# BMS028B_Interface.net
KiCad netlist of a schematic drawn in Altium Designer
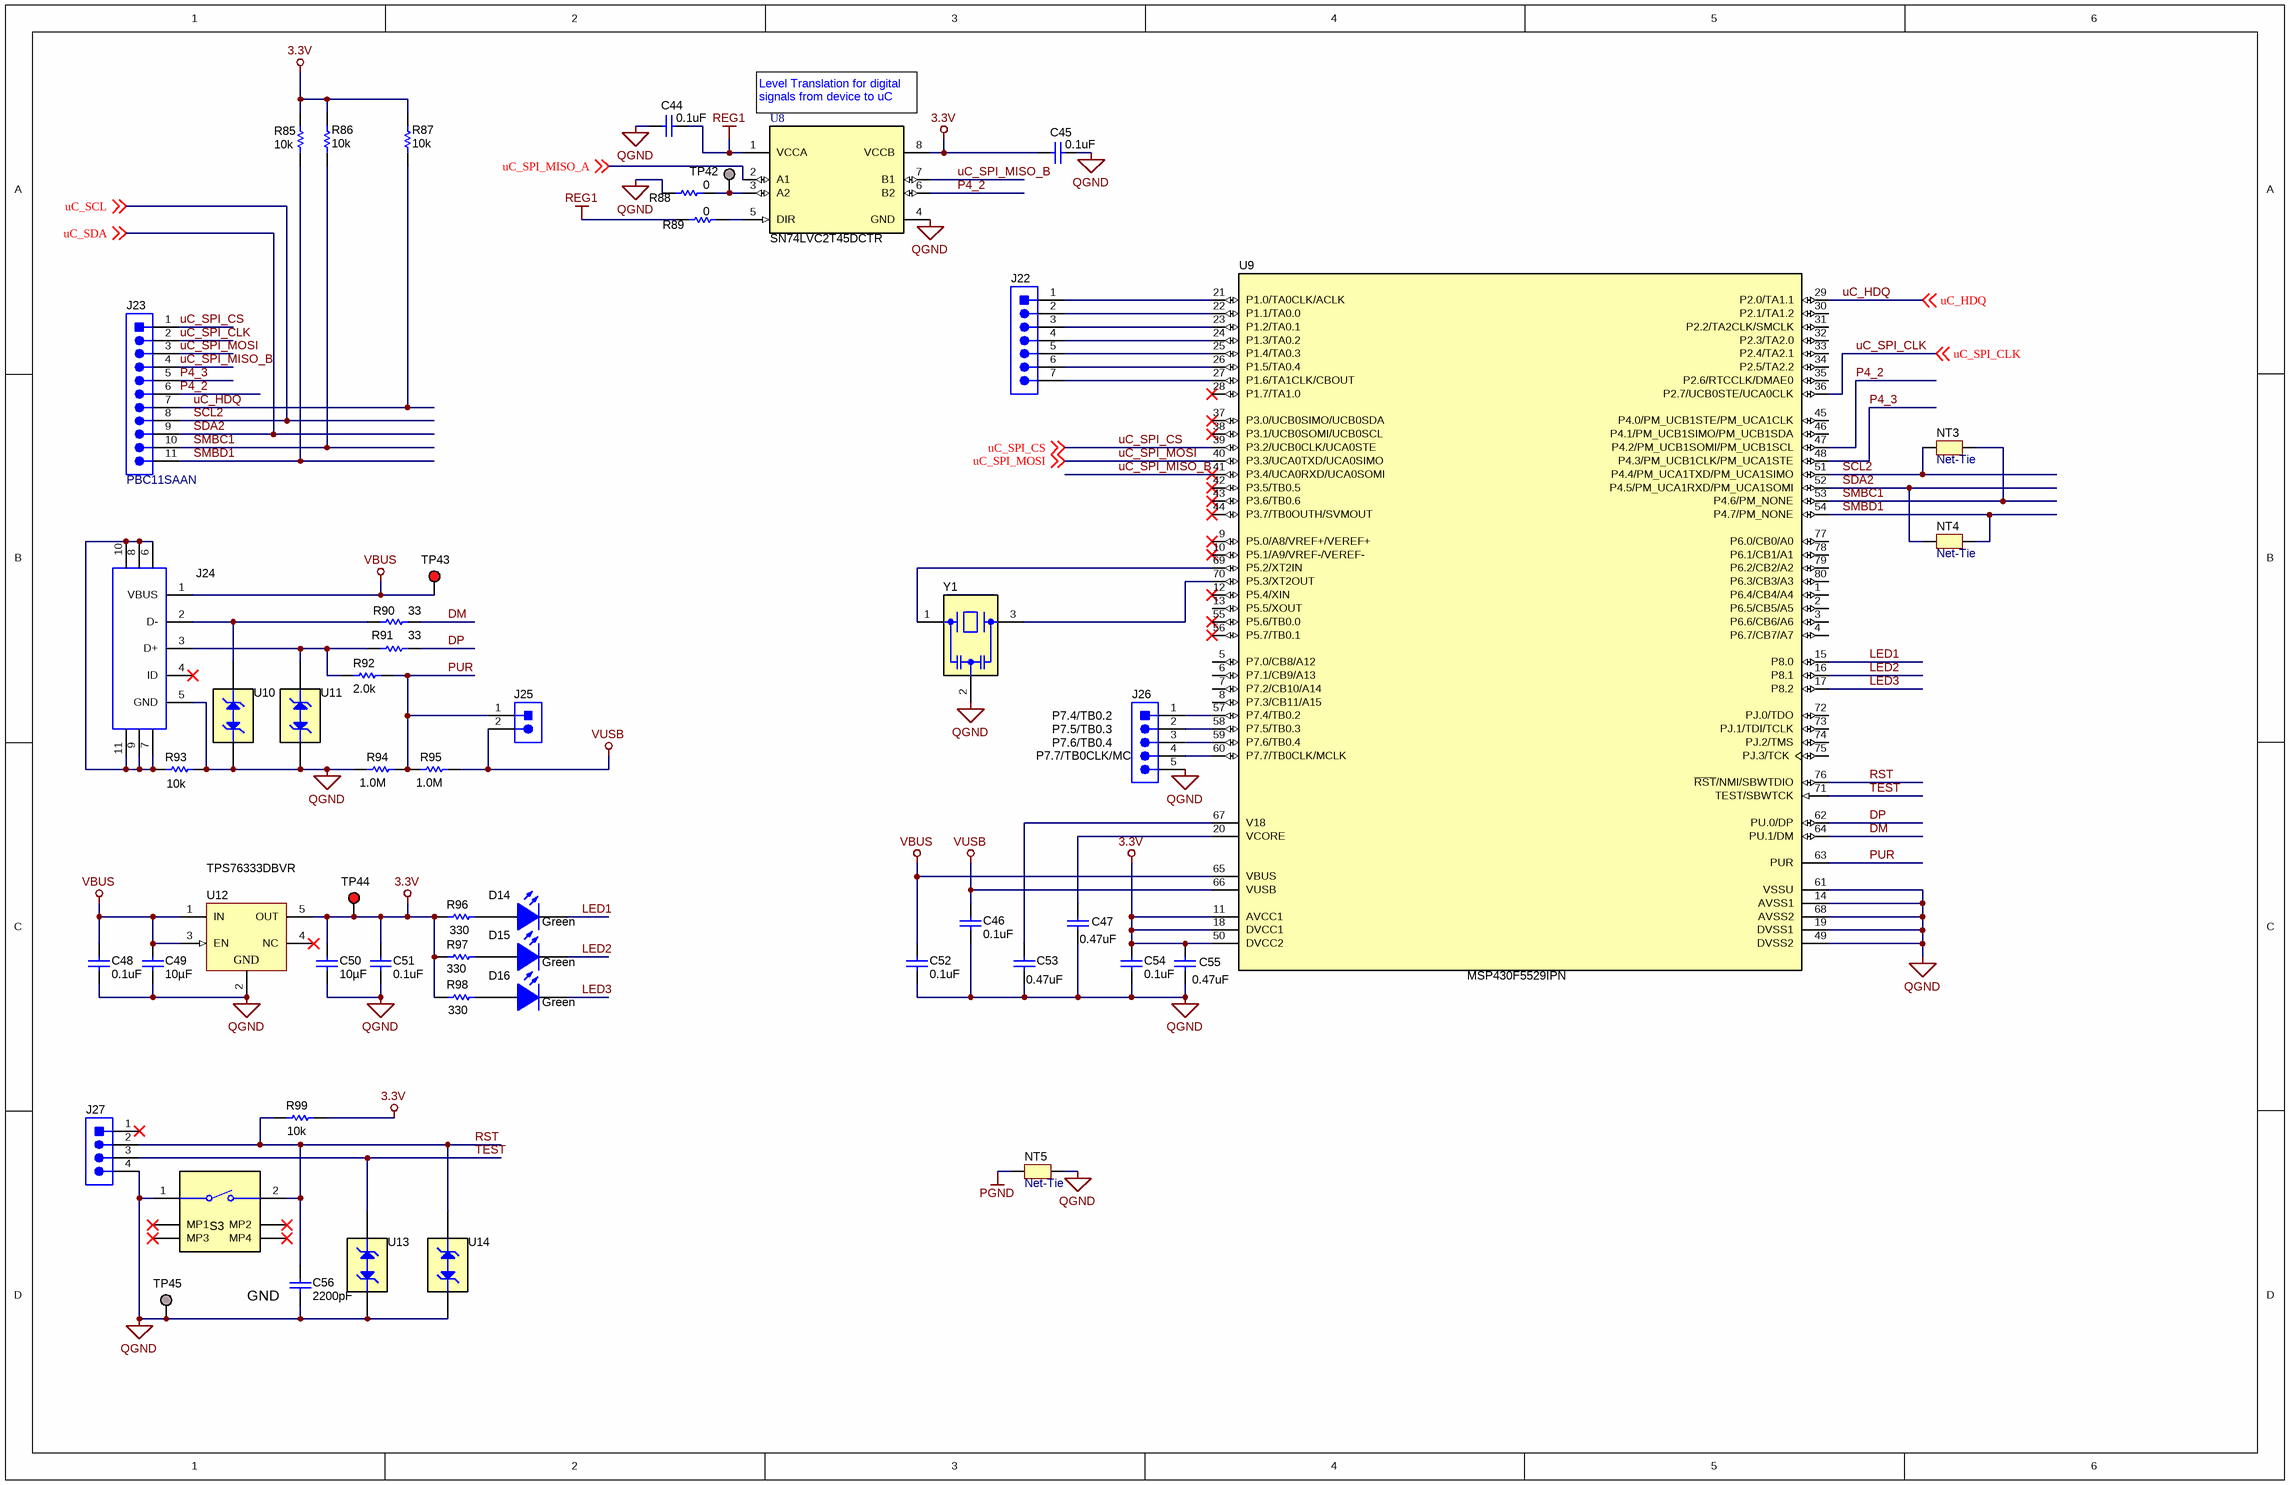
[diagram p0: BMS028B_Interface.SchDoc]

(export (version "E")
  (design (tool "Eeschema 10.0.6"))
  (components
    (comp (ref "C44")
      (value "885012205037")
      (footprint "0402")
      (description "CAP, CERM, 0.1 uF, 16 V, +/- 10%, X7R, 0402")
      (fields
        (field (name "VALUEDISPLAYED") "0.1uF")
        (field (name "MANUFACTURER") "Wurth Elektronik")
        (field (name "PUBLISHER") "Texas Instruments")
      )
      (libsource (lib "Altium Vault - TI") (part "Capacitor"))
    )
    (comp (ref "C45")
      (value "885012205037")
      (footprint "0402")
      (description "CAP, CERM, 0.1 uF, 16 V, +/- 10%, X7R, 0402")
      (fields
        (field (name "VALUEDISPLAYED") "0.1uF")
        (field (name "MANUFACTURER") "Wurth Elektronik")
        (field (name "PUBLISHER") "Texas Instruments")
      )
      (libsource (lib "Altium Vault - TI") (part "Capacitor"))
    )
    (comp (ref "C46")
      (value "885012205037")
      (footprint "0402")
      (description "CAP, CERM, 0.1 uF, 16 V, +/- 10%, X7R, 0402")
      (fields
        (field (name "VALUEDISPLAYED") "0.1uF")
        (field (name "MANUFACTURER") "Wurth Elektronik")
        (field (name "PUBLISHER") "Texas Instruments")
      )
      (libsource (lib "Altium Vault - TI") (part "Capacitor"))
    )
    (comp (ref "C47")
      (value "Capacitor")
      (footprint "0402")
      (description "CAP, CERM, 0.47 uF, 6.3 V, +/- 10%, X5R, 0402")
      (fields
        (field (name "PARTNUMBER") "04026D474KAT2A")
        (field (name "VALUEDISPLAYED") "0.47uF")
        (field (name "MANUFACTURER") "AVX")
        (field (name "PUBLISHER") "Texas Instruments")
      )
      (libsource (lib "Altium Vault - TI") (part "Capacitor"))
    )
    (comp (ref "C48")
      (value "885012205037")
      (footprint "0402")
      (description "CAP, CERM, 0.1 uF, 16 V, +/- 10%, X7R, 0402")
      (fields
        (field (name "VALUEDISPLAYED") "0.1uF")
        (field (name "MANUFACTURER") "Wurth Elektronik")
        (field (name "PUBLISHER") "Texas Instruments")
      )
      (libsource (lib "Altium Vault - TI") (part "Capacitor"))
    )
    (comp (ref "C49")
      (value "CL21A106KOQNNNG")
      (footprint "0805_HV")
      (description "CAP, CERM, 10 µF, 16 V,+/- 10%, X5R, 0805")
      (fields
        (field (name "VALUEDISPLAYED") "10µF")
        (field (name "MANUFACTURER") "Samsung Electro-Mechanics")
      )
      (libsource (lib "Altium Vault - TI") (part "Capacitor"))
    )
    (comp (ref "C50")
      (value "CL21A106KOQNNNG")
      (footprint "0805_HV")
      (description "CAP, CERM, 10 µF, 16 V,+/- 10%, X5R, 0805")
      (fields
        (field (name "VALUEDISPLAYED") "10µF")
        (field (name "MANUFACTURER") "Samsung Electro-Mechanics")
      )
      (libsource (lib "Altium Vault - TI") (part "Capacitor"))
    )
    (comp (ref "C51")
      (value "885012205037")
      (footprint "0402")
      (description "CAP, CERM, 0.1 uF, 16 V, +/- 10%, X7R, 0402")
      (fields
        (field (name "VALUEDISPLAYED") "0.1uF")
        (field (name "MANUFACTURER") "Wurth Elektronik")
        (field (name "PUBLISHER") "Texas Instruments")
      )
      (libsource (lib "Altium Vault - TI") (part "Capacitor"))
    )
    (comp (ref "C52")
      (value "885012205037")
      (footprint "0402")
      (description "CAP, CERM, 0.1 uF, 16 V, +/- 10%, X7R, 0402")
      (fields
        (field (name "VALUEDISPLAYED") "0.1uF")
        (field (name "MANUFACTURER") "Wurth Elektronik")
        (field (name "PUBLISHER") "Texas Instruments")
      )
      (libsource (lib "Altium Vault - TI") (part "Capacitor"))
    )
    (comp (ref "C53")
      (value "Capacitor")
      (footprint "0402")
      (description "CAP, CERM, 0.47 uF, 6.3 V, +/- 10%, X5R, 0402")
      (fields
        (field (name "PARTNUMBER") "04026D474KAT2A")
        (field (name "VALUEDISPLAYED") "0.47uF")
        (field (name "MANUFACTURER") "AVX")
        (field (name "PUBLISHER") "Texas Instruments")
      )
      (libsource (lib "Altium Vault - TI") (part "Capacitor"))
    )
    (comp (ref "C54")
      (value "885012205037")
      (footprint "0402")
      (description "CAP, CERM, 0.1 uF, 16 V, +/- 10%, X7R, 0402")
      (fields
        (field (name "VALUEDISPLAYED") "0.1uF")
        (field (name "MANUFACTURER") "Wurth Elektronik")
        (field (name "PUBLISHER") "Texas Instruments")
      )
      (libsource (lib "Altium Vault - TI") (part "Capacitor"))
    )
    (comp (ref "C55")
      (value "Capacitor")
      (footprint "0402")
      (description "CAP, CERM, 0.47 uF, 6.3 V, +/- 10%, X5R, 0402")
      (fields
        (field (name "PARTNUMBER") "04026D474KAT2A")
        (field (name "VALUEDISPLAYED") "0.47uF")
        (field (name "MANUFACTURER") "AVX")
        (field (name "PUBLISHER") "Texas Instruments")
      )
      (libsource (lib "Altium Vault - TI") (part "Capacitor"))
    )
    (comp (ref "C56")
      (value "885012205008")
      (footprint "0402")
      (description "CAP, CERM, 2200 pF, 10 V, +/- 10%, X7R, 0402")
      (fields
        (field (name "VALUEDISPLAYED") "2200pF")
        (field (name "MANUFACTURER") "Wurth Elektronik")
        (field (name "PUBLISHER") "Texas Instruments")
      )
      (libsource (lib "Altium Vault - TI") (part "Capacitor"))
    )
    (comp (ref "D14")
      (value "Green")
      (footprint "WL-SMCW_GREEN")
      (description "LED, Green, SMD")
      (fields (field (name "MANUFACTURER") "Wurth Elektronik") (field (name "PARTNUMBER") "150060VS75000"))
      (libsource (lib "Altium Vault - TI") (part "CMP-0002894-2"))
    )
    (comp (ref "D15")
      (value "Green")
      (footprint "WL-SMCW_GREEN")
      (description "LED, Green, SMD")
      (fields (field (name "MANUFACTURER") "Wurth Elektronik") (field (name "PARTNUMBER") "150060VS75000"))
      (libsource (lib "Altium Vault - TI") (part "CMP-0002894-2"))
    )
    (comp (ref "D16")
      (value "Green")
      (footprint "WL-SMCW_GREEN")
      (description "LED, Green, SMD")
      (fields (field (name "MANUFACTURER") "Wurth Elektronik") (field (name "PARTNUMBER") "150060VS75000"))
      (libsource (lib "Altium Vault - TI") (part "CMP-0002894-2"))
    )
    (comp (ref "J22")
      (value "PBC07SAAN")
      (footprint "Sullins_xxC07SAAN")
      (description "Header, 2.54 mm, 7x1, Gold, TH")
      (fields
        (field (name "MANUFACTURER") "Sullins Connector Solutions")
        (field (name "PUBLISHER") "Texas Instruments")
      )
      (libsource (lib "Altium Vault - TI") (part "CMP-0054584-1"))
    )
    (comp (ref "J23")
      (value "PBC11SAAN")
      (footprint "Sullins_xxC11SAAN")
      (description "Header, 2.54 mm, 11x1, Gold, TH")
      (fields
        (field (name "MANUFACTURER") "Sullins Connector Solutions")
        (field (name "PUBLISHER") "Texas Instruments")
      )
      (libsource (lib "Altium Vault - TI") (part "Header_11x1"))
    )
    (comp (ref "J24")
      (value "CONN_USB_5Pos-6Shld")
      (footprint "Molex_47346-1001")
      (description "Receptacle, Micro-USB Type B, 0.65 mm, 5x1, R/A, Bottom Mount SMT")
      (fields
        (field (name "PARTNUMBER") "47346-1001")
        (field (name "MANUFACTURER") "Molex")
        (field (name "SYMBOLCREATOR") "a0411947")
        (field (name "PUBLISHER") "Texas Instruments")
      )
      (libsource (lib "Altium Vault - TI") (part "CONN_USB_5Pos-6Shld"))
    )
    (comp (ref "J25")
      (value "61300211121")
      (footprint "WURTH_61300211121")
      (description "Header, 2.54 mm, 2x1, Gold, TH")
      (fields (field (name "MANUFACTURER") "Wurth Elektronik"))
      (libsource (lib "Altium Vault - TI") (part "CMP-0054794-2"))
    )
    (comp (ref "J26")
      (value "PEC05SAAN")
      (footprint "Sullins_PxC05SAAN")
      (description "Header, 2.54mm, 5x1, Tin, TH")
      (fields
        (field (name "MANUFACTURER") "Sullins Connector Solutions")
        (field (name "PUBLISHER") "Texas Instruments")
      )
      (libsource (lib "Altium Vault - TI") (part "CMP-0054597-1"))
    )
    (comp (ref "J27")
      (value "22284043")
      (footprint "Molex_0022284043")
      (description "Header, 2.54mm, 4x1, Tin, TH")
      (fields (field (name "MANUFACTURER") "Molex") (field (name "PUBLISHER") "Texas Instruments"))
      (libsource (lib "Altium Vault - TI") (part "CMP-0055331-1"))
    )
    (comp (ref "NT3")
      (value "Net-Tie")
      (footprint "Net-Tie_10mil")
      (description "Single point connection between nets.")
      (libsource (lib "") (part "Net-Tie_1"))
    )
    (comp (ref "NT4")
      (value "Net-Tie")
      (footprint "Net-Tie_10mil")
      (description "Single point connection between nets.")
      (libsource (lib "") (part "Net-Tie_1"))
    )
    (comp (ref "NT5")
      (value "Net-Tie")
      (footprint "Net-Tie_0805_HV_NoOverlay")
      (description "Single point connection between nets.")
      (libsource (lib "Altium Vault - TI") (part "Net-Tie"))
    )
    (comp (ref "R85")
      (value "CRCW060310K0JNEA")
      (footprint "0603")
      (description "RES, 10 k, 5%, 0.1 W, AEC-Q200 Grade 0, 0603")
      (fields (field (name "MANUFACTURER") "Vishay-Dale") (field (name "VALUEDISPLAYED") "10k"))
      (libsource (lib "Altium Vault - TI") (part "Resistor"))
    )
    (comp (ref "R86")
      (value "CRCW060310K0JNEA")
      (footprint "0603")
      (description "RES, 10 k, 5%, 0.1 W, AEC-Q200 Grade 0, 0603")
      (fields (field (name "MANUFACTURER") "Vishay-Dale") (field (name "VALUEDISPLAYED") "10k"))
      (libsource (lib "Altium Vault - TI") (part "CMP-0025701-4"))
    )
    (comp (ref "R87")
      (value "CRCW060310K0JNEA")
      (footprint "0603")
      (description "RES, 10 k, 5%, 0.1 W, AEC-Q200 Grade 0, 0603")
      (fields (field (name "MANUFACTURER") "Vishay-Dale") (field (name "VALUEDISPLAYED") "10k"))
      (libsource (lib "Altium Vault - TI") (part "Resistor"))
    )
    (comp (ref "R88")
      (value "CRCW06030000Z0EA")
      (footprint "0603")
      (description "RES, 0, 5%, 0.1 W, AEC-Q200 Grade 0, 0603")
      (fields (field (name "MANUFACTURER") "Vishay-Dale") (field (name "VALUEDISPLAYED") "0"))
      (libsource (lib "Altium Vault - TI") (part "Resistor"))
    )
    (comp (ref "R89")
      (value "CRCW06030000Z0EA")
      (footprint "0603")
      (description "RES, 0, 5%, 0.1 W, AEC-Q200 Grade 0, 0603")
      (fields (field (name "MANUFACTURER") "Vishay-Dale") (field (name "VALUEDISPLAYED") "0"))
      (libsource (lib "Altium Vault - TI") (part "Resistor"))
    )
    (comp (ref "R90")
      (value "Resistor")
      (footprint "0402")
      (description "RES, 33, 5%, 0.063 W, AEC-Q200 Grade 0, 0402")
      (fields
        (field (name "PARTNUMBER") "CRCW040233R0JNED")
        (field (name "VALUEDISPLAYED") "33")
        (field (name "MANUFACTURER") "Vishay-Dale")
        (field (name "PUBLISHER") "Texas Instruments")
      )
      (libsource (lib "Altium Vault - TI") (part "Resistor"))
    )
    (comp (ref "R91")
      (value "Resistor")
      (footprint "0402")
      (description "RES, 33, 5%, 0.063 W, AEC-Q200 Grade 0, 0402")
      (fields
        (field (name "PARTNUMBER") "CRCW040233R0JNED")
        (field (name "VALUEDISPLAYED") "33")
        (field (name "MANUFACTURER") "Vishay-Dale")
        (field (name "PUBLISHER") "Texas Instruments")
      )
      (libsource (lib "Altium Vault - TI") (part "Resistor"))
    )
    (comp (ref "R92")
      (value "Resistor")
      (footprint "0402")
      (description "RES, 2.0 k, 5%, 0.063 W, AEC-Q200 Grade 0, 0402")
      (fields
        (field (name "PARTNUMBER") "CRCW04022K00JNED")
        (field (name "VALUEDISPLAYED") "2.0k")
        (field (name "MANUFACTURER") "Vishay-Dale")
        (field (name "PUBLISHER") "Texas Instruments")
      )
      (libsource (lib "Altium Vault - TI") (part "Resistor"))
    )
    (comp (ref "R93")
      (value "Resistor")
      (footprint "0402")
      (description "RES, 10 k, 5%, 0.063 W, AEC-Q200 Grade 0, 0402")
      (fields
        (field (name "PARTNUMBER") "CRCW040210K0JNED")
        (field (name "VALUEDISPLAYED") "10k")
        (field (name "MANUFACTURER") "Vishay-Dale")
        (field (name "PUBLISHER") "Texas Instruments")
      )
      (libsource (lib "Altium Vault - TI") (part "Resistor"))
    )
    (comp (ref "R94")
      (value "Resistor")
      (footprint "0402")
      (description "RES, 1.0 M, 5%, 0.063 W, AEC-Q200 Grade 0, 0402")
      (fields
        (field (name "PARTNUMBER") "CRCW04021M00JNED")
        (field (name "VALUEDISPLAYED") "1.0M")
        (field (name "MANUFACTURER") "Vishay-Dale")
        (field (name "PUBLISHER") "Texas Instruments")
      )
      (libsource (lib "Altium Vault - TI") (part "Resistor"))
    )
    (comp (ref "R95")
      (value "Resistor")
      (footprint "0402")
      (description "RES, 1.0 M, 5%, 0.063 W, AEC-Q200 Grade 0, 0402")
      (fields
        (field (name "PARTNUMBER") "CRCW04021M00JNED")
        (field (name "VALUEDISPLAYED") "1.0M")
        (field (name "MANUFACTURER") "Vishay-Dale")
        (field (name "PUBLISHER") "Texas Instruments")
      )
      (libsource (lib "Altium Vault - TI") (part "Resistor"))
    )
    (comp (ref "R96")
      (value "Resistor")
      (footprint "0402")
      (description "RES, 330, 1%, 0.1 W, AEC-Q200 Grade 0, 0402")
      (fields
        (field (name "PARTNUMBER") "ERJ-2RKF3300X")
        (field (name "VALUEDISPLAYED") "330")
        (field (name "MANUFACTURER") "Panasonic")
        (field (name "PUBLISHER") "Texas Instruments")
      )
      (libsource (lib "Altium Vault - TI") (part "Resistor"))
    )
    (comp (ref "R97")
      (value "Resistor")
      (footprint "0402")
      (description "RES, 330, 1%, 0.1 W, AEC-Q200 Grade 0, 0402")
      (fields
        (field (name "PARTNUMBER") "ERJ-2RKF3300X")
        (field (name "VALUEDISPLAYED") "330")
        (field (name "MANUFACTURER") "Panasonic")
        (field (name "PUBLISHER") "Texas Instruments")
      )
      (libsource (lib "Altium Vault - TI") (part "Resistor"))
    )
    (comp (ref "R98")
      (value "Resistor")
      (footprint "0402")
      (description "RES, 330, 1%, 0.1 W, AEC-Q200 Grade 0, 0402")
      (fields
        (field (name "PARTNUMBER") "ERJ-2RKF3300X")
        (field (name "VALUEDISPLAYED") "330")
        (field (name "MANUFACTURER") "Panasonic")
        (field (name "PUBLISHER") "Texas Instruments")
      )
      (libsource (lib "Altium Vault - TI") (part "Resistor"))
    )
    (comp (ref "R99")
      (value "Resistor")
      (footprint "0402")
      (description "RES, 10 k, 5%, 0.063 W, AEC-Q200 Grade 0, 0402")
      (fields
        (field (name "PARTNUMBER") "CRCW040210K0JNED")
        (field (name "VALUEDISPLAYED") "10k")
        (field (name "MANUFACTURER") "Vishay-Dale")
        (field (name "PUBLISHER") "Texas Instruments")
      )
      (libsource (lib "Altium Vault - TI") (part "Resistor"))
    )
    (comp (ref "S3")
      (value "PTS820 J20M SMTR LFS")
      (footprint "SW_PTS820")
      (description "Switch, SPST-NO,  Off-Mom, 0.05A, 12VDC, SMD")
      (fields (field (name "MANUFACTURER") "C&K Components") (field (name "PUBLISHER") "Texas Instruments"))
      (libsource (lib "Altium Vault - TI") (part "SW_SPST_12_4MP"))
    )
    (comp (ref "TP42")
      (value "TESTPOINT")
      (footprint "TP_50MIL-25MILHOLE")
      (description "TEST POINT.  No entry in BOM.")
      (libsource (lib "Altium Vault - TI") (part "TESTPOINT"))
    )
    (comp (ref "TP43")
      (value "5005")
      (footprint "Keystone5005")
      (description "Test Point, Compact, Red, TH")
      (fields (field (name "MANUFACTURER") "Keystone") (field (name "PUBLISHER") "Texas Instruments"))
      (libsource (lib "Altium Vault - TI") (part "5005"))
    )
    (comp (ref "TP44")
      (value "5005")
      (footprint "Keystone5005")
      (description "Test Point, Compact, Red, TH")
      (fields (field (name "MANUFACTURER") "Keystone") (field (name "PUBLISHER") "Texas Instruments"))
      (libsource (lib "Altium Vault - TI") (part "5005"))
    )
    (comp (ref "TP45")
      (value "TESTPOINT")
      (footprint "TP_SM_1MM")
      (description "1mm Test Point, SMT")
      (fields
        (field (name "PARTNUMBER") "TP_SM_1MM")
        (field (name "MANUFACTURER") "Any")
        (field (name "PUBLISHER") "Texas Instruments")
      )
      (libsource (lib "Altium Vault - TI") (part "TESTPOINT"))
    )
    (comp (ref "U8")
      (value "SN74LVC2T45DCTR")
      (footprint "DCT0008A_N")
      (fields
        (field (name "MANUFACTURER") "Texas Instruments")
        (field (name "GENERIC PART NUMBER") "SN74LVC2T45")
        (field (name "PARTNUMBER") "SN74LVC2T45DCTR")
      )
      (libsource (lib "Altium Vault - TI") (part "TI-SN74XVC2T45-8"))
    )
    (comp (ref "U9")
      (value "CMP-0038965-1")
      (footprint "PN0080A_N")
      (fields (field (name "PARTNUMBER") "MSP430F5529IPN") (field (name "MANUFACTURER") "Texas Instruments"))
      (libsource (lib "Altium Vault - TI") (part "TI-MSP430F552X_A-PN80"))
    )
    (comp (ref "U10")
      (value "TPD1E10B06DPYT")
      (footprint "DPY0002A")
      (description "Single-Channel ESD in 0402 Package With 10pF Capacitance and 6V Breakdown, DPY0002A (X1SON-2)")
      (fields
        (field (name "MANUFACTURER") "Texas Instruments")
        (field (name "ALTERNATE PARTNUMBER") "TPD1E10B06DPYR")
      )
      (libsource (lib "Altium Vault - TI") (part "CMP-0043094-3"))
    )
    (comp (ref "U11")
      (value "TPD1E10B06DPYT")
      (footprint "DPY0002A")
      (description "Single-Channel ESD in 0402 Package With 10pF Capacitance and 6V Breakdown, DPY0002A (X1SON-2)")
      (fields
        (field (name "MANUFACTURER") "Texas Instruments")
        (field (name "ALTERNATE PARTNUMBER") "TPD1E10B06DPYR")
      )
      (libsource (lib "Altium Vault - TI") (part "CMP-0043094-3"))
    )
    (comp (ref "U12")
      (value "CMP-0035539-1")
      (footprint "DBV0005A_N")
      (fields (field (name "MANUFACTURER") "Texas Instruments") (field (name "PARTNUMBER") "TPS76333DBVR"))
      (libsource (lib "Altium Vault - TI") (part "CMP-0035539-1"))
    )
    (comp (ref "U13")
      (value "TPD1E10B06DPYT")
      (footprint "DPY0002A")
      (description "Single-Channel ESD in 0402 Package With 10pF Capacitance and 6V Breakdown, DPY0002A (X1SON-2)")
      (fields
        (field (name "MANUFACTURER") "Texas Instruments")
        (field (name "ALTERNATE PARTNUMBER") "TPD1E10B06DPYR")
      )
      (libsource (lib "Altium Vault - TI") (part "CMP-0043094-3"))
    )
    (comp (ref "U14")
      (value "TPD1E10B06DPYT")
      (footprint "DPY0002A")
      (description "Single-Channel ESD in 0402 Package With 10pF Capacitance and 6V Breakdown, DPY0002A (X1SON-2)")
      (fields
        (field (name "MANUFACTURER") "Texas Instruments")
        (field (name "ALTERNATE PARTNUMBER") "TPD1E10B06DPYR")
      )
      (libsource (lib "Altium Vault - TI") (part "CMP-0043094-3"))
    )
    (comp (ref "Y1")
      (value "CSTCR4M00G55B-R0")
      (footprint "Murata_CSTCR_G")
      (description "Resonator, 4 MHz, 39 pF, AEC-Q200 Grade 1, SMD")
      (fields (field (name "MANUFACTURER") "MuRata"))
      (libsource (lib "Altium Vault - TI") (part "CMP-0084387-1"))
    )
  )
  (nets
    (net (code "2") (name "/DM") (class "Default")
      (node (ref "R90") (pin "2") (pinfunction "2_2") (pintype "passive"))
      (node (ref "U9") (pin "64") (pinfunction "PU.1/DM_64") (pintype "bidirectional"))
    )
    (net (code "3") (name "/DP") (class "Default")
      (node (ref "R91") (pin "2") (pinfunction "2_2") (pintype "passive"))
      (node (ref "U9") (pin "62") (pinfunction "PU.0/DP_62") (pintype "bidirectional"))
    )
    (net (code "4") (name "/LED1") (class "Default")
      (node (ref "D14") (pin "1") (pinfunction "K_1") (pintype "passive"))
      (node (ref "U9") (pin "15") (pinfunction "P8.0_15") (pintype "bidirectional"))
    )
    (net (code "5") (name "/LED2") (class "Default")
      (node (ref "D15") (pin "1") (pinfunction "K_1") (pintype "passive"))
      (node (ref "U9") (pin "16") (pinfunction "P8.1_16") (pintype "bidirectional"))
    )
    (net (code "6") (name "/LED3") (class "Default")
      (node (ref "D16") (pin "1") (pinfunction "K_1") (pintype "passive"))
      (node (ref "U9") (pin "17") (pinfunction "P8.2_17") (pintype "bidirectional"))
    )
    (net (code "7") (name "/P4_2") (class "Default")
      (node (ref "J23") (pin "6") (pinfunction "6_6") (pintype "passive"))
      (node (ref "U8") (pin "6") (pinfunction "B2_6") (pintype "bidirectional"))
      (node (ref "U9") (pin "47") (pinfunction "P4.2/PM_UCB1SOMI/PM_UCB1SCL_47") (pintype "bidirectional"))
    )
    (net (code "8") (name "/P4_3") (class "Default")
      (node (ref "J23") (pin "5") (pinfunction "5_5") (pintype "passive"))
      (node (ref "U9") (pin "48") (pinfunction "P4.3/PM_UCB1CLK/PM_UCA1STE_48") (pintype "bidirectional"))
    )
    (net (code "9") (name "/PUR") (class "Default")
      (node (ref "J25") (pin "1") (pinfunction "1_1") (pintype "passive"))
      (node (ref "R92") (pin "1") (pinfunction "1_1") (pintype "passive"))
      (node (ref "R94") (pin "2") (pinfunction "2_2") (pintype "passive"))
      (node (ref "R95") (pin "1") (pinfunction "1_1") (pintype "passive"))
      (node (ref "U9") (pin "63") (pinfunction "PUR_63") (pintype "passive"))
    )
    (net (code "10") (name "/RST") (class "Default")
      (node (ref "C56") (pin "1") (pinfunction "1_1") (pintype "passive"))
      (node (ref "J27") (pin "2") (pinfunction "2_2") (pintype "passive"))
      (node (ref "R99") (pin "1") (pinfunction "1_1") (pintype "passive"))
      (node (ref "S3") (pin "2") (pinfunction "2_2") (pintype "passive"))
      (node (ref "U14") (pin "1") (pinfunction "K_1") (pintype "passive"))
      (node (ref "U9") (pin "76") (pinfunction "~{RST}/NMI/SBWTDIO_76") (pintype "bidirectional"))
    )
    (net (code "11") (name "/SMBC1") (class "Default")
      (node (ref "J23") (pin "10") (pinfunction "10_10") (pintype "passive"))
      (node (ref "NT3") (pin "2") (pinfunction "2_2") (pintype "passive"))
      (node (ref "R86") (pin "2") (pinfunction "2_2") (pintype "passive"))
      (node (ref "U9") (pin "53") (pinfunction "P4.6/PM_NONE_53") (pintype "bidirectional"))
    )
    (net (code "12") (name "/SMBD1") (class "Default")
      (node (ref "J23") (pin "11") (pinfunction "11_11") (pintype "passive"))
      (node (ref "NT4") (pin "2") (pinfunction "2_2") (pintype "passive"))
      (node (ref "R85") (pin "2") (pinfunction "2_2") (pintype "passive"))
      (node (ref "U9") (pin "54") (pinfunction "P4.7/PM_NONE_54") (pintype "bidirectional"))
    )
    (net (code "13") (name "/TEST") (class "Default")
      (node (ref "J27") (pin "3") (pinfunction "3_3") (pintype "passive"))
      (node (ref "U13") (pin "1") (pinfunction "K_1") (pintype "passive"))
      (node (ref "U9") (pin "71") (pinfunction "TEST/SBWTCK_71") (pintype "input"))
    )
    (net (code "14") (name "/uC_SPI_MISO_B") (class "Default")
      (node (ref "J23") (pin "4") (pinfunction "4_4") (pintype "passive"))
      (node (ref "U8") (pin "7") (pinfunction "B1_7") (pintype "bidirectional"))
      (node (ref "U9") (pin "41") (pinfunction "P3.4/UCA0RXD/UCA0SOMI_41") (pintype "bidirectional"))
    )
    (net (code "15") (name "3.3V") (class "Default")
      (node (ref "C45") (pin "2") (pinfunction "2_2") (pintype "passive"))
      (node (ref "C50") (pin "1") (pinfunction "1_1") (pintype "passive"))
      (node (ref "C51") (pin "1") (pinfunction "1_1") (pintype "passive"))
      (node (ref "C54") (pin "1") (pinfunction "1_1") (pintype "passive"))
      (node (ref "C55") (pin "1") (pinfunction "1_1") (pintype "passive"))
      (node (ref "R85") (pin "1") (pinfunction "1_1") (pintype "passive"))
      (node (ref "R86") (pin "1") (pinfunction "1_1") (pintype "passive"))
      (node (ref "R87") (pin "1") (pinfunction "1_1") (pintype "passive"))
      (node (ref "R96") (pin "2") (pinfunction "2_2") (pintype "passive"))
      (node (ref "R97") (pin "2") (pinfunction "2_2") (pintype "passive"))
      (node (ref "R98") (pin "2") (pinfunction "2_2") (pintype "passive"))
      (node (ref "R99") (pin "2") (pinfunction "2_2") (pintype "passive"))
      (node (ref "TP44") (pin "1") (pintype "passive"))
      (node (ref "U12") (pin "5") (pinfunction "OUT_5") (pintype "power_in"))
      (node (ref "U8") (pin "8") (pinfunction "VCCB_8") (pintype "power_in"))
      (node (ref "U9") (pin "11") (pinfunction "AVCC1_11") (pintype "power_in"))
      (node (ref "U9") (pin "18") (pinfunction "DVCC1_18") (pintype "power_in"))
      (node (ref "U9") (pin "50") (pinfunction "DVCC2_50") (pintype "power_in"))
    )
    (net (code "16") (name "Net-(D14-A)") (class "Default")
      (node (ref "D14") (pin "2") (pinfunction "A_2") (pintype "passive"))
      (node (ref "R96") (pin "1") (pinfunction "1_1") (pintype "passive"))
    )
    (net (code "17") (name "Net-(D15-A)") (class "Default")
      (node (ref "D15") (pin "2") (pinfunction "A_2") (pintype "passive"))
      (node (ref "R97") (pin "1") (pinfunction "1_1") (pintype "passive"))
    )
    (net (code "18") (name "Net-(D16-A)") (class "Default")
      (node (ref "D16") (pin "2") (pinfunction "A_2") (pintype "passive"))
      (node (ref "R98") (pin "1") (pinfunction "1_1") (pintype "passive"))
    )
    (net (code "19") (name "Net-(J24-D+)") (class "Default")
      (node (ref "J24") (pin "3") (pinfunction "D+_3") (pintype "passive"))
      (node (ref "R91") (pin "1") (pinfunction "1_1") (pintype "passive"))
      (node (ref "R92") (pin "2") (pinfunction "2_2") (pintype "passive"))
      (node (ref "U11") (pin "1") (pinfunction "K_1") (pintype "passive"))
    )
    (net (code "20") (name "Net-(J24-D-)") (class "Default")
      (node (ref "J24") (pin "2") (pinfunction "D-_2") (pintype "passive"))
      (node (ref "R90") (pin "1") (pinfunction "1_1") (pintype "passive"))
      (node (ref "U10") (pin "1") (pinfunction "K_1") (pintype "passive"))
    )
    (net (code "21") (name "Net-(J24-Pad10)") (class "Default")
      (node (ref "J24") (pin "10") (pinfunction "10_10") (pintype "passive"))
      (node (ref "J24") (pin "11") (pinfunction "11_11") (pintype "passive"))
      (node (ref "J24") (pin "6") (pinfunction "6_6") (pintype "passive"))
      (node (ref "J24") (pin "7") (pinfunction "7_7") (pintype "passive"))
      (node (ref "J24") (pin "8") (pinfunction "8_8") (pintype "passive"))
      (node (ref "J24") (pin "9") (pinfunction "9_9") (pintype "passive"))
      (node (ref "R93") (pin "2") (pinfunction "2_2") (pintype "passive"))
    )
    (net (code "22") (name "Net-(U8-A2)") (class "Default")
      (node (ref "R88") (pin "2") (pinfunction "2_2") (pintype "passive"))
      (node (ref "TP42") (pin "1") (pintype "passive"))
      (node (ref "U8") (pin "3") (pinfunction "A2_3") (pintype "bidirectional"))
    )
    (net (code "23") (name "Net-(U8-DIR)") (class "Default")
      (node (ref "R89") (pin "2") (pinfunction "2_2") (pintype "passive"))
      (node (ref "U8") (pin "5") (pinfunction "DIR_5") (pintype "input"))
    )
    (net (code "24") (name "Net-(U9-P1.0{slash}TA0CLK{slash}ACLK)") (class "Default")
      (node (ref "J22") (pin "1") (pinfunction "1_1") (pintype "passive"))
      (node (ref "U9") (pin "21") (pinfunction "P1.0/TA0CLK/ACLK_21") (pintype "bidirectional"))
    )
    (net (code "25") (name "Net-(U9-P1.1{slash}TA0.0)") (class "Default")
      (node (ref "J22") (pin "2") (pinfunction "2_2") (pintype "passive"))
      (node (ref "U9") (pin "22") (pinfunction "P1.1/TA0.0_22") (pintype "bidirectional"))
    )
    (net (code "26") (name "Net-(U9-P1.2{slash}TA0.1)") (class "Default")
      (node (ref "J22") (pin "3") (pinfunction "3_3") (pintype "passive"))
      (node (ref "U9") (pin "23") (pinfunction "P1.2/TA0.1_23") (pintype "bidirectional"))
    )
    (net (code "27") (name "Net-(U9-P1.3{slash}TA0.2)") (class "Default")
      (node (ref "J22") (pin "4") (pinfunction "4_4") (pintype "passive"))
      (node (ref "U9") (pin "24") (pinfunction "P1.3/TA0.2_24") (pintype "bidirectional"))
    )
    (net (code "28") (name "Net-(U9-P1.4{slash}TA0.3)") (class "Default")
      (node (ref "J22") (pin "5") (pinfunction "5_5") (pintype "passive"))
      (node (ref "U9") (pin "25") (pinfunction "P1.4/TA0.3_25") (pintype "bidirectional"))
    )
    (net (code "29") (name "Net-(U9-P1.5{slash}TA0.4)") (class "Default")
      (node (ref "J22") (pin "6") (pinfunction "6_6") (pintype "passive"))
      (node (ref "U9") (pin "26") (pinfunction "P1.5/TA0.4_26") (pintype "bidirectional"))
    )
    (net (code "30") (name "Net-(U9-P1.6{slash}TA1CLK{slash}CBOUT)") (class "Default")
      (node (ref "J22") (pin "7") (pinfunction "7_7") (pintype "passive"))
      (node (ref "U9") (pin "27") (pinfunction "P1.6/TA1CLK/CBOUT_27") (pintype "bidirectional"))
    )
    (net (code "31") (name "Net-(U9-P5.2{slash}XT2IN)") (class "Default")
      (node (ref "U9") (pin "69") (pinfunction "P5.2/XT2IN_69") (pintype "bidirectional"))
      (node (ref "Y1") (pin "1") (pinfunction "In_1") (pintype "passive"))
    )
    (net (code "32") (name "Net-(U9-P5.3{slash}XT2OUT)") (class "Default")
      (node (ref "U9") (pin "70") (pinfunction "P5.3/XT2OUT_70") (pintype "bidirectional"))
      (node (ref "Y1") (pin "3") (pinfunction "Out_3") (pintype "passive"))
    )
    (net (code "33") (name "Net-(U9-P7.4{slash}TB0.2)") (class "Default")
      (node (ref "J26") (pin "1") (pinfunction "1_1") (pintype "passive"))
      (node (ref "U9") (pin "57") (pinfunction "P7.4/TB0.2_57") (pintype "bidirectional"))
    )
    (net (code "34") (name "Net-(U9-P7.5{slash}TB0.3)") (class "Default")
      (node (ref "J26") (pin "2") (pinfunction "2_2") (pintype "passive"))
      (node (ref "U9") (pin "58") (pinfunction "P7.5/TB0.3_58") (pintype "bidirectional"))
    )
    (net (code "35") (name "Net-(U9-P7.6{slash}TB0.4)") (class "Default")
      (node (ref "J26") (pin "3") (pinfunction "3_3") (pintype "passive"))
      (node (ref "U9") (pin "59") (pinfunction "P7.6/TB0.4_59") (pintype "bidirectional"))
    )
    (net (code "36") (name "Net-(U9-P7.7{slash}TB0CLK{slash}MCLK)") (class "Default")
      (node (ref "J26") (pin "4") (pinfunction "4_4") (pintype "passive"))
      (node (ref "U9") (pin "60") (pinfunction "P7.7/TB0CLK/MCLK_60") (pintype "bidirectional"))
    )
    (net (code "37") (name "Net-(U9-V18)") (class "Default")
      (node (ref "C53") (pin "1") (pinfunction "1_1") (pintype "passive"))
      (node (ref "U9") (pin "67") (pinfunction "V18_67") (pintype "passive"))
    )
    (net (code "38") (name "Net-(U9-VCORE)") (class "Default")
      (node (ref "C47") (pin "1") (pinfunction "1_1") (pintype "passive"))
      (node (ref "U9") (pin "20") (pinfunction "VCORE_20") (pintype "passive"))
    )
    (net (code "39") (name "PGND") (class "Default")
      (node (ref "NT5") (pin "2") (pinfunction "2_2") (pintype "passive"))
    )
    (net (code "40") (name "QGND") (class "Default")
      (node (ref "C44") (pin "1") (pinfunction "1_1") (pintype "passive"))
      (node (ref "C45") (pin "1") (pinfunction "1_1") (pintype "passive"))
      (node (ref "C46") (pin "2") (pinfunction "2_2") (pintype "passive"))
      (node (ref "C47") (pin "2") (pinfunction "2_2") (pintype "passive"))
      (node (ref "C48") (pin "2") (pinfunction "2_2") (pintype "passive"))
      (node (ref "C49") (pin "2") (pinfunction "2_2") (pintype "passive"))
      (node (ref "C50") (pin "2") (pinfunction "2_2") (pintype "passive"))
      (node (ref "C51") (pin "2") (pinfunction "2_2") (pintype "passive"))
      (node (ref "C52") (pin "2") (pinfunction "2_2") (pintype "passive"))
      (node (ref "C53") (pin "2") (pinfunction "2_2") (pintype "passive"))
      (node (ref "C54") (pin "2") (pinfunction "2_2") (pintype "passive"))
      (node (ref "C55") (pin "2") (pinfunction "2_2") (pintype "passive"))
      (node (ref "C56") (pin "2") (pinfunction "2_2") (pintype "passive"))
      (node (ref "J24") (pin "5") (pinfunction "GND_5") (pintype "passive"))
      (node (ref "J26") (pin "5") (pinfunction "5_5") (pintype "passive"))
      (node (ref "J27") (pin "4") (pinfunction "4_4") (pintype "passive"))
      (node (ref "NT5") (pin "1") (pinfunction "1_1") (pintype "passive"))
      (node (ref "R88") (pin "1") (pinfunction "1_1") (pintype "passive"))
      (node (ref "R93") (pin "1") (pinfunction "1_1") (pintype "passive"))
      (node (ref "R94") (pin "1") (pinfunction "1_1") (pintype "passive"))
      (node (ref "S3") (pin "1") (pinfunction "1_1") (pintype "passive"))
      (node (ref "TP45") (pin "1") (pintype "passive"))
      (node (ref "U10") (pin "2") (pinfunction "A_2") (pintype "passive"))
      (node (ref "U11") (pin "2") (pinfunction "A_2") (pintype "passive"))
      (node (ref "U12") (pin "2") (pinfunction "GND_2") (pintype "power_in"))
      (node (ref "U13") (pin "2") (pinfunction "A_2") (pintype "passive"))
      (node (ref "U14") (pin "2") (pinfunction "A_2") (pintype "passive"))
      (node (ref "U8") (pin "4") (pinfunction "GND_4") (pintype "power_in"))
      (node (ref "U9") (pin "14") (pinfunction "AVSS1_14") (pintype "power_in"))
      (node (ref "U9") (pin "19") (pinfunction "DVSS1_19") (pintype "power_in"))
      (node (ref "U9") (pin "49") (pinfunction "DVSS2_49") (pintype "power_in"))
      (node (ref "U9") (pin "61") (pinfunction "VSSU_61") (pintype "power_in"))
      (node (ref "U9") (pin "68") (pinfunction "AVSS2_68") (pintype "power_in"))
      (node (ref "Y1") (pin "2") (pinfunction "GND_2") (pintype "passive"))
    )
    (net (code "41") (name "REG1") (class "Default")
      (node (ref "C44") (pin "2") (pinfunction "2_2") (pintype "passive"))
      (node (ref "R89") (pin "1") (pinfunction "1_1") (pintype "passive"))
      (node (ref "U8") (pin "1") (pinfunction "VCCA_1") (pintype "power_in"))
    )
    (net (code "42") (name "VBUS") (class "Default")
      (node (ref "C48") (pin "1") (pinfunction "1_1") (pintype "passive"))
      (node (ref "C49") (pin "1") (pinfunction "1_1") (pintype "passive"))
      (node (ref "C52") (pin "1") (pinfunction "1_1") (pintype "passive"))
      (node (ref "J24") (pin "1") (pinfunction "VBUS_1") (pintype "passive"))
      (node (ref "TP43") (pin "1") (pintype "passive"))
      (node (ref "U12") (pin "1") (pinfunction "IN_1") (pintype "power_in"))
      (node (ref "U12") (pin "3") (pinfunction "EN_3") (pintype "input"))
      (node (ref "U9") (pin "65") (pinfunction "VBUS_65") (pintype "power_in"))
    )
    (net (code "43") (name "VUSB") (class "Default")
      (node (ref "C46") (pin "1") (pinfunction "1_1") (pintype "passive"))
      (node (ref "J25") (pin "2") (pinfunction "2_2") (pintype "passive"))
      (node (ref "R95") (pin "2") (pinfunction "2_2") (pintype "passive"))
      (node (ref "U9") (pin "66") (pinfunction "VUSB_66") (pintype "power_in"))
    )
    (net (code "44") (name "uC_HDQ") (class "Default")
      (node (ref "J23") (pin "7") (pinfunction "7_7") (pintype "passive"))
      (node (ref "R87") (pin "2") (pinfunction "2_2") (pintype "passive"))
      (node (ref "U9") (pin "29") (pinfunction "P2.0/TA1.1_29") (pintype "bidirectional"))
    )
    (net (code "45") (name "uC_SCL") (class "Default")
      (node (ref "J23") (pin "8") (pinfunction "8_8") (pintype "passive"))
      (node (ref "NT3") (pin "1") (pinfunction "1_1") (pintype "passive"))
      (node (ref "U9") (pin "51") (pinfunction "P4.4/PM_UCA1TXD/PM_UCA1SIMO_51") (pintype "bidirectional"))
    )
    (net (code "46") (name "uC_SDA") (class "Default")
      (node (ref "J23") (pin "9") (pinfunction "9_9") (pintype "passive"))
      (node (ref "NT4") (pin "1") (pinfunction "1_1") (pintype "passive"))
      (node (ref "U9") (pin "52") (pinfunction "P4.5/PM_UCA1RXD/PM_UCA1SOMI_52") (pintype "bidirectional"))
    )
    (net (code "47") (name "uC_SPI_CLK") (class "Default")
      (node (ref "J23") (pin "2") (pinfunction "2_2") (pintype "passive"))
      (node (ref "U9") (pin "36") (pinfunction "P2.7/UCB0STE/UCA0CLK_36") (pintype "bidirectional"))
    )
    (net (code "48") (name "uC_SPI_CS") (class "Default")
      (node (ref "J23") (pin "1") (pinfunction "1_1") (pintype "passive"))
      (node (ref "U9") (pin "39") (pinfunction "P3.2/UCB0CLK/UCA0STE_39") (pintype "bidirectional"))
    )
    (net (code "49") (name "uC_SPI_MISO_A") (class "Default")
      (node (ref "U8") (pin "2") (pinfunction "A1_2") (pintype "bidirectional"))
    )
    (net (code "50") (name "uC_SPI_MOSI") (class "Default")
      (node (ref "J23") (pin "3") (pinfunction "3_3") (pintype "passive"))
      (node (ref "U9") (pin "40") (pinfunction "P3.3/UCA0TXD/UCA0SIMO_40") (pintype "bidirectional"))
    )
    (net (code "51") (name "unconnected-(J24-ID-Pad4)") (class "Default")
      (node (ref "J24") (pin "4") (pinfunction "ID_4") (pintype "passive+no_connect"))
    )
    (net (code "52") (name "unconnected-(J27-Pad1)") (class "Default")
      (node (ref "J27") (pin "1") (pinfunction "1_1") (pintype "passive+no_connect"))
    )
    (net (code "53") (name "unconnected-(S3-PadMP1)") (class "Default")
      (node (ref "S3") (pin "MP1") (pinfunction "MP1_MP1") (pintype "passive+no_connect"))
    )
    (net (code "54") (name "unconnected-(S3-PadMP2)") (class "Default")
      (node (ref "S3") (pin "MP2") (pinfunction "MP2_MP2") (pintype "passive+no_connect"))
    )
    (net (code "55") (name "unconnected-(S3-PadMP3)") (class "Default")
      (node (ref "S3") (pin "MP3") (pinfunction "MP3_MP3") (pintype "passive+no_connect"))
    )
    (net (code "56") (name "unconnected-(S3-PadMP4)") (class "Default")
      (node (ref "S3") (pin "MP4") (pinfunction "MP4_MP4") (pintype "passive+no_connect"))
    )
    (net (code "57") (name "unconnected-(U9-P1.7{slash}TA1.0-Pad28)") (class "Default")
      (node (ref "U9") (pin "28") (pinfunction "P1.7/TA1.0_28") (pintype "bidirectional+no_connect"))
    )
    (net (code "58") (name "unconnected-(U9-P2.1{slash}TA1.2-Pad30)") (class "Default")
      (node (ref "U9") (pin "30") (pinfunction "P2.1/TA1.2_30") (pintype "bidirectional"))
    )
    (net (code "59") (name "unconnected-(U9-P2.2{slash}TA2CLK{slash}SMCLK-Pad31)") (class "Default")
      (node (ref "U9") (pin "31") (pinfunction "P2.2/TA2CLK/SMCLK_31") (pintype "bidirectional"))
    )
    (net (code "60") (name "unconnected-(U9-P2.3{slash}TA2.0-Pad32)") (class "Default")
      (node (ref "U9") (pin "32") (pinfunction "P2.3/TA2.0_32") (pintype "bidirectional"))
    )
    (net (code "61") (name "unconnected-(U9-P2.4{slash}TA2.1-Pad33)") (class "Default")
      (node (ref "U9") (pin "33") (pinfunction "P2.4/TA2.1_33") (pintype "bidirectional"))
    )
    (net (code "62") (name "unconnected-(U9-P2.5{slash}TA2.2-Pad34)") (class "Default")
      (node (ref "U9") (pin "34") (pinfunction "P2.5/TA2.2_34") (pintype "bidirectional"))
    )
    (net (code "63") (name "unconnected-(U9-P2.6{slash}RTCCLK{slash}DMAE0-Pad35)") (class "Default")
      (node (ref "U9") (pin "35") (pinfunction "P2.6/RTCCLK/DMAE0_35") (pintype "bidirectional"))
    )
    (net (code "64") (name "unconnected-(U9-P3.0{slash}UCB0SIMO{slash}UCB0SDA-Pad37)") (class "Default")
      (node (ref "U9") (pin "37") (pinfunction "P3.0/UCB0SIMO/UCB0SDA_37") (pintype "bidirectional+no_connect"))
    )
    (net (code "65") (name "unconnected-(U9-P3.1{slash}UCB0SOMI{slash}UCB0SCL-Pad38)") (class "Default")
      (node (ref "U9") (pin "38") (pinfunction "P3.1/UCB0SOMI/UCB0SCL_38") (pintype "bidirectional+no_connect"))
    )
    (net (code "66") (name "unconnected-(U9-P3.5{slash}TB0.5-Pad42)") (class "Default")
      (node (ref "U9") (pin "42") (pinfunction "P3.5/TB0.5_42") (pintype "bidirectional+no_connect"))
    )
    (net (code "67") (name "unconnected-(U9-P3.6{slash}TB0.6-Pad43)") (class "Default")
      (node (ref "U9") (pin "43") (pinfunction "P3.6/TB0.6_43") (pintype "bidirectional+no_connect"))
    )
    (net (code "68") (name "unconnected-(U9-P3.7{slash}TB0OUTH{slash}SVMOUT-Pad44)") (class "Default")
      (node (ref "U9") (pin "44") (pinfunction "P3.7/TB0OUTH/SVMOUT_44") (pintype "bidirectional+no_connect"))
    )
    (net (code "69") (name "unconnected-(U9-P4.0{slash}PM_UCB1STE{slash}PM_UCA1CLK-Pad45)") (class "Default")
      (node (ref "U9") (pin "45") (pinfunction "P4.0/PM_UCB1STE/PM_UCA1CLK_45") (pintype "bidirectional"))
    )
    (net (code "70") (name "unconnected-(U9-P4.1{slash}PM_UCB1SIMO{slash}PM_UCB1SDA-Pad46)") (class "Default")
      (node (ref "U9") (pin "46") (pinfunction "P4.1/PM_UCB1SIMO/PM_UCB1SDA_46") (pintype "bidirectional"))
    )
    (net (code "71") (name "unconnected-(U9-P5.0{slash}A8{slash}VREF+{slash}VEREF+-Pad9)") (class "Default")
      (node (ref "U9") (pin "9") (pinfunction "P5.0/A8/VREF+/VEREF+_9") (pintype "bidirectional+no_connect"))
    )
    (net (code "72") (name "unconnected-(U9-P5.1{slash}A9{slash}VREF-{slash}VEREF--Pad10)") (class "Default")
      (node (ref "U9") (pin "10") (pinfunction "P5.1/A9/VREF-/VEREF-_10") (pintype "bidirectional+no_connect"))
    )
    (net (code "73") (name "unconnected-(U9-P5.4{slash}XIN-Pad12)") (class "Default")
      (node (ref "U9") (pin "12") (pinfunction "P5.4/XIN_12") (pintype "bidirectional+no_connect"))
    )
    (net (code "74") (name "unconnected-(U9-P5.5{slash}XOUT-Pad13)") (class "Default")
      (node (ref "U9") (pin "13") (pinfunction "P5.5/XOUT_13") (pintype "bidirectional"))
    )
    (net (code "75") (name "unconnected-(U9-P5.6{slash}TB0.0-Pad55)") (class "Default")
      (node (ref "U9") (pin "55") (pinfunction "P5.6/TB0.0_55") (pintype "bidirectional+no_connect"))
    )
    (net (code "76") (name "unconnected-(U9-P5.7{slash}TB0.1-Pad56)") (class "Default")
      (node (ref "U9") (pin "56") (pinfunction "P5.7/TB0.1_56") (pintype "bidirectional+no_connect"))
    )
    (net (code "77") (name "unconnected-(U9-P6.0{slash}CB0{slash}A0-Pad77)") (class "Default")
      (node (ref "U9") (pin "77") (pinfunction "P6.0/CB0/A0_77") (pintype "bidirectional"))
    )
    (net (code "78") (name "unconnected-(U9-P6.1{slash}CB1{slash}A1-Pad78)") (class "Default")
      (node (ref "U9") (pin "78") (pinfunction "P6.1/CB1/A1_78") (pintype "bidirectional"))
    )
    (net (code "79") (name "unconnected-(U9-P6.2{slash}CB2{slash}A2-Pad79)") (class "Default")
      (node (ref "U9") (pin "79") (pinfunction "P6.2/CB2/A2_79") (pintype "bidirectional"))
    )
    (net (code "80") (name "unconnected-(U9-P6.3{slash}CB3{slash}A3-Pad80)") (class "Default")
      (node (ref "U9") (pin "80") (pinfunction "P6.3/CB3/A3_80") (pintype "bidirectional"))
    )
    (net (code "81") (name "unconnected-(U9-P6.4{slash}CB4{slash}A4-Pad1)") (class "Default")
      (node (ref "U9") (pin "1") (pinfunction "P6.4/CB4/A4_1") (pintype "bidirectional"))
    )
    (net (code "82") (name "unconnected-(U9-P6.5{slash}CB5{slash}A5-Pad2)") (class "Default")
      (node (ref "U9") (pin "2") (pinfunction "P6.5/CB5/A5_2") (pintype "bidirectional"))
    )
    (net (code "83") (name "unconnected-(U9-P6.6{slash}CB6{slash}A6-Pad3)") (class "Default")
      (node (ref "U9") (pin "3") (pinfunction "P6.6/CB6/A6_3") (pintype "bidirectional"))
    )
    (net (code "84") (name "unconnected-(U9-P6.7{slash}CB7{slash}A7-Pad4)") (class "Default")
      (node (ref "U9") (pin "4") (pinfunction "P6.7/CB7/A7_4") (pintype "bidirectional"))
    )
    (net (code "85") (name "unconnected-(U9-P7.0{slash}CB8{slash}A12-Pad5)") (class "Default")
      (node (ref "U9") (pin "5") (pinfunction "P7.0/CB8/A12_5") (pintype "bidirectional"))
    )
    (net (code "86") (name "unconnected-(U9-P7.1{slash}CB9{slash}A13-Pad6)") (class "Default")
      (node (ref "U9") (pin "6") (pinfunction "P7.1/CB9/A13_6") (pintype "bidirectional"))
    )
    (net (code "87") (name "unconnected-(U9-P7.2{slash}CB10{slash}A14-Pad7)") (class "Default")
      (node (ref "U9") (pin "7") (pinfunction "P7.2/CB10/A14_7") (pintype "bidirectional"))
    )
    (net (code "88") (name "unconnected-(U9-P7.3{slash}CB11{slash}A15-Pad8)") (class "Default")
      (node (ref "U9") (pin "8") (pinfunction "P7.3/CB11/A15_8") (pintype "bidirectional"))
    )
    (net (code "89") (name "unconnected-(U9-PJ.0{slash}TDO-Pad72)") (class "Default")
      (node (ref "U9") (pin "72") (pinfunction "PJ.0/TDO_72") (pintype "bidirectional"))
    )
    (net (code "90") (name "unconnected-(U9-PJ.1{slash}TDI{slash}TCLK-Pad73)") (class "Default")
      (node (ref "U9") (pin "73") (pinfunction "PJ.1/TDI/TCLK_73") (pintype "bidirectional"))
    )
    (net (code "91") (name "unconnected-(U9-PJ.2{slash}TMS-Pad74)") (class "Default")
      (node (ref "U9") (pin "74") (pinfunction "PJ.2/TMS_74") (pintype "bidirectional"))
    )
    (net (code "92") (name "unconnected-(U9-PJ.3{slash}TCK-Pad75)") (class "Default")
      (node (ref "U9") (pin "75") (pinfunction "PJ.3/TCK_75") (pintype "bidirectional"))
    )
    (net (code "93") (name "unconnected-(U12-NC-Pad4)") (class "Default")
      (node (ref "U12") (pin "4") (pinfunction "NC_4") (pintype "passive+no_connect"))
    )
  )
)
